# SCH_praktikum-gib-mir-mal-ne-wago_V1_0_2.net
KiCad netlist of a schematic drawn in EasyEDA
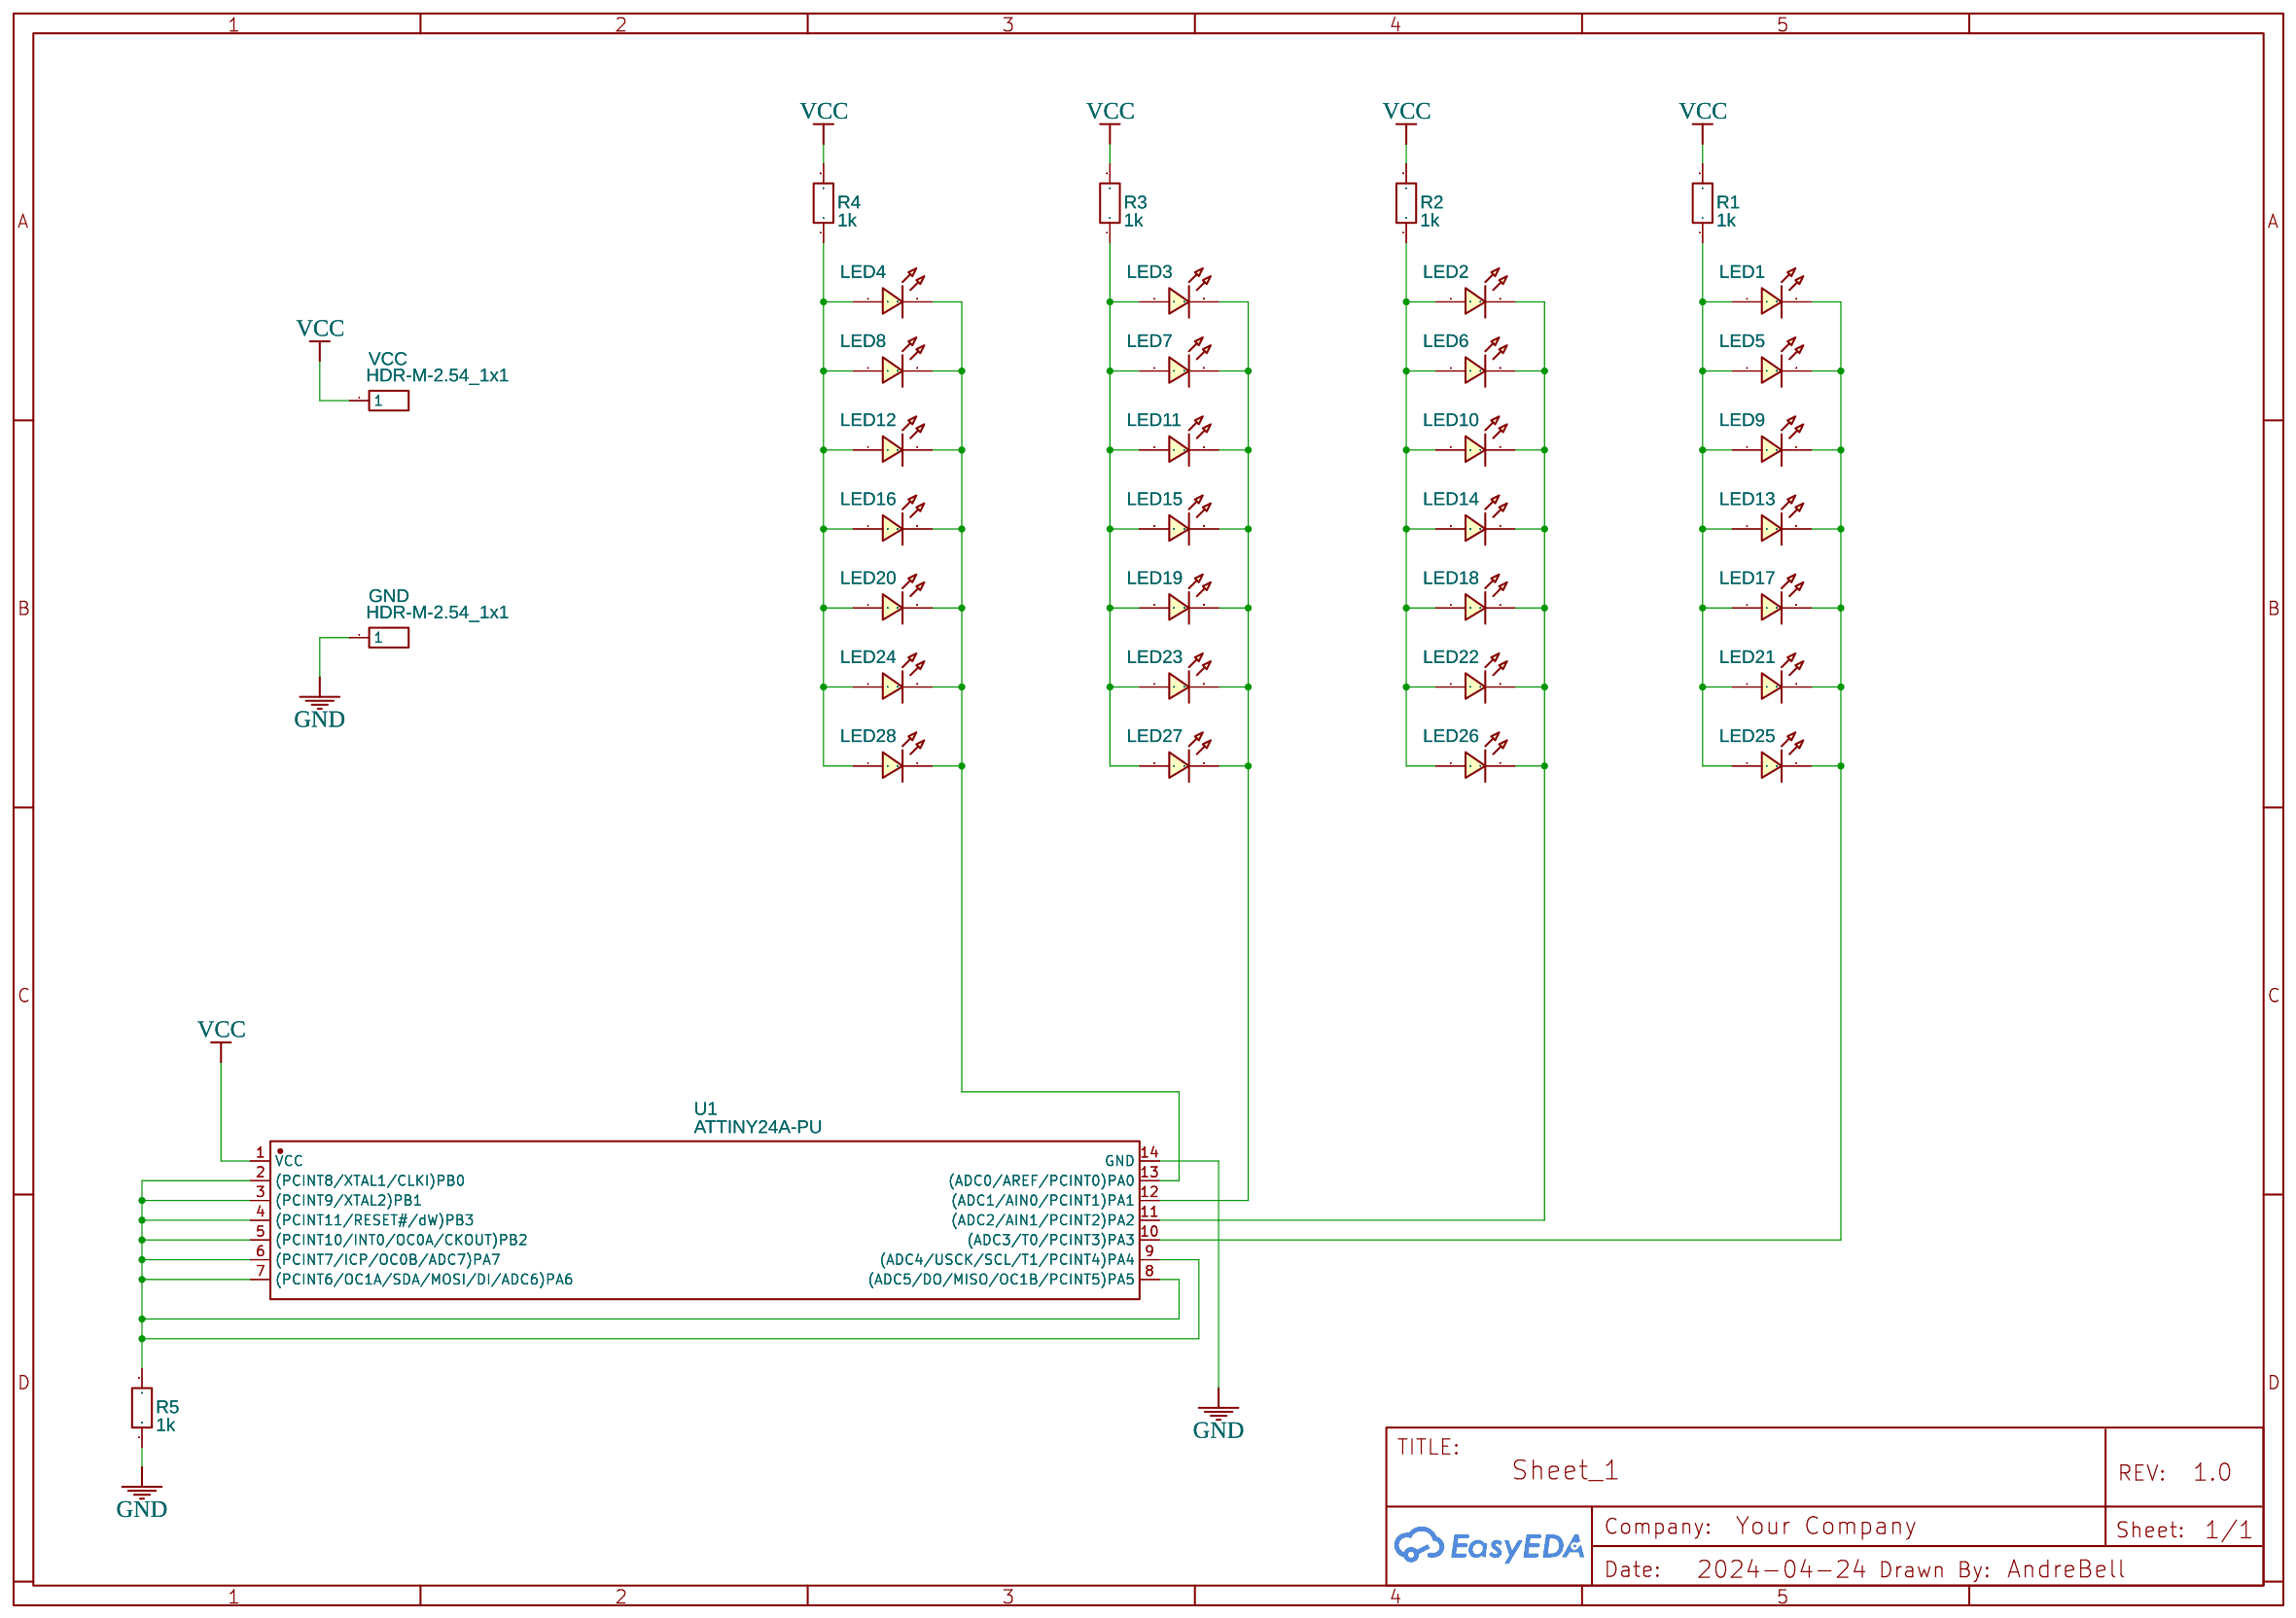
[diagram p0: schematic sheet]

(export (version "E")
  (design (tool "Eeschema 10.0.6"))
  (components
    (comp (ref "GND") (value "HDR-M-2.54_1x1") (libsource (lib "") (part "HDR-M-2.54_1x1")))
    (comp (ref "LED1")
      (value "LED-TH-3mm_G")
      (fields
        (field (name "Manufacturer Part") "204-10SYGD/S530-E3")
        (field (name "Manufacturer") "EVERLIGHT(台湾亿光)")
      )
      (libsource (lib "") (part "LED-TH-3mm_G"))
    )
    (comp (ref "LED2")
      (value "LED-TH-3mm_G")
      (fields
        (field (name "Manufacturer Part") "204-10SYGD/S530-E3")
        (field (name "Manufacturer") "EVERLIGHT(台湾亿光)")
      )
      (libsource (lib "") (part "LED-TH-3mm_G"))
    )
    (comp (ref "LED3")
      (value "LED-TH-3mm_G")
      (fields
        (field (name "Manufacturer Part") "204-10SYGD/S530-E3")
        (field (name "Manufacturer") "EVERLIGHT(台湾亿光)")
      )
      (libsource (lib "") (part "LED-TH-3mm_G"))
    )
    (comp (ref "LED4")
      (value "LED-TH-3mm_G")
      (fields
        (field (name "Manufacturer Part") "204-10SYGD/S530-E3")
        (field (name "Manufacturer") "EVERLIGHT(台湾亿光)")
      )
      (libsource (lib "") (part "LED-TH-3mm_G"))
    )
    (comp (ref "LED5")
      (value "LED-TH-3mm_G")
      (fields
        (field (name "Manufacturer Part") "204-10SYGD/S530-E3")
        (field (name "Manufacturer") "EVERLIGHT(台湾亿光)")
      )
      (libsource (lib "") (part "LED-TH-3mm_G"))
    )
    (comp (ref "LED6")
      (value "LED-TH-3mm_G")
      (fields
        (field (name "Manufacturer Part") "204-10SYGD/S530-E3")
        (field (name "Manufacturer") "EVERLIGHT(台湾亿光)")
      )
      (libsource (lib "") (part "LED-TH-3mm_G"))
    )
    (comp (ref "LED7")
      (value "LED-TH-3mm_G")
      (fields
        (field (name "Manufacturer Part") "204-10SYGD/S530-E3")
        (field (name "Manufacturer") "EVERLIGHT(台湾亿光)")
      )
      (libsource (lib "") (part "LED-TH-3mm_G"))
    )
    (comp (ref "LED8")
      (value "LED-TH-3mm_G")
      (fields
        (field (name "Manufacturer Part") "204-10SYGD/S530-E3")
        (field (name "Manufacturer") "EVERLIGHT(台湾亿光)")
      )
      (libsource (lib "") (part "LED-TH-3mm_G"))
    )
    (comp (ref "LED9")
      (value "LED-TH-3mm_G")
      (fields
        (field (name "Manufacturer Part") "204-10SYGD/S530-E3")
        (field (name "Manufacturer") "EVERLIGHT(台湾亿光)")
      )
      (libsource (lib "") (part "LED-TH-3mm_G"))
    )
    (comp (ref "LED10")
      (value "LED-TH-3mm_G")
      (fields
        (field (name "Manufacturer Part") "204-10SYGD/S530-E3")
        (field (name "Manufacturer") "EVERLIGHT(台湾亿光)")
      )
      (libsource (lib "") (part "LED-TH-3mm_G"))
    )
    (comp (ref "LED11")
      (value "LED-TH-3mm_G")
      (fields
        (field (name "Manufacturer Part") "204-10SYGD/S530-E3")
        (field (name "Manufacturer") "EVERLIGHT(台湾亿光)")
      )
      (libsource (lib "") (part "LED-TH-3mm_G"))
    )
    (comp (ref "LED12")
      (value "LED-TH-3mm_G")
      (fields
        (field (name "Manufacturer Part") "204-10SYGD/S530-E3")
        (field (name "Manufacturer") "EVERLIGHT(台湾亿光)")
      )
      (libsource (lib "") (part "LED-TH-3mm_G"))
    )
    (comp (ref "LED13")
      (value "LED-TH-3mm_G")
      (fields
        (field (name "Manufacturer Part") "204-10SYGD/S530-E3")
        (field (name "Manufacturer") "EVERLIGHT(台湾亿光)")
      )
      (libsource (lib "") (part "LED-TH-3mm_G"))
    )
    (comp (ref "LED14")
      (value "LED-TH-3mm_G")
      (fields
        (field (name "Manufacturer Part") "204-10SYGD/S530-E3")
        (field (name "Manufacturer") "EVERLIGHT(台湾亿光)")
      )
      (libsource (lib "") (part "LED-TH-3mm_G"))
    )
    (comp (ref "LED15")
      (value "LED-TH-3mm_G")
      (fields
        (field (name "Manufacturer Part") "204-10SYGD/S530-E3")
        (field (name "Manufacturer") "EVERLIGHT(台湾亿光)")
      )
      (libsource (lib "") (part "LED-TH-3mm_G"))
    )
    (comp (ref "LED16")
      (value "LED-TH-3mm_G")
      (fields
        (field (name "Manufacturer Part") "204-10SYGD/S530-E3")
        (field (name "Manufacturer") "EVERLIGHT(台湾亿光)")
      )
      (libsource (lib "") (part "LED-TH-3mm_G"))
    )
    (comp (ref "LED17")
      (value "LED-TH-3mm_G")
      (fields
        (field (name "Manufacturer Part") "204-10SYGD/S530-E3")
        (field (name "Manufacturer") "EVERLIGHT(台湾亿光)")
      )
      (libsource (lib "") (part "LED-TH-3mm_G"))
    )
    (comp (ref "LED18")
      (value "LED-TH-3mm_G")
      (fields
        (field (name "Manufacturer Part") "204-10SYGD/S530-E3")
        (field (name "Manufacturer") "EVERLIGHT(台湾亿光)")
      )
      (libsource (lib "") (part "LED-TH-3mm_G"))
    )
    (comp (ref "LED19")
      (value "LED-TH-3mm_G")
      (fields
        (field (name "Manufacturer Part") "204-10SYGD/S530-E3")
        (field (name "Manufacturer") "EVERLIGHT(台湾亿光)")
      )
      (libsource (lib "") (part "LED-TH-3mm_G"))
    )
    (comp (ref "LED20")
      (value "LED-TH-3mm_G")
      (fields
        (field (name "Manufacturer Part") "204-10SYGD/S530-E3")
        (field (name "Manufacturer") "EVERLIGHT(台湾亿光)")
      )
      (libsource (lib "") (part "LED-TH-3mm_G"))
    )
    (comp (ref "LED21")
      (value "LED-TH-3mm_G")
      (fields
        (field (name "Manufacturer Part") "204-10SYGD/S530-E3")
        (field (name "Manufacturer") "EVERLIGHT(台湾亿光)")
      )
      (libsource (lib "") (part "LED-TH-3mm_G"))
    )
    (comp (ref "LED22")
      (value "LED-TH-3mm_G")
      (fields
        (field (name "Manufacturer Part") "204-10SYGD/S530-E3")
        (field (name "Manufacturer") "EVERLIGHT(台湾亿光)")
      )
      (libsource (lib "") (part "LED-TH-3mm_G"))
    )
    (comp (ref "LED23")
      (value "LED-TH-3mm_G")
      (fields
        (field (name "Manufacturer Part") "204-10SYGD/S530-E3")
        (field (name "Manufacturer") "EVERLIGHT(台湾亿光)")
      )
      (libsource (lib "") (part "LED-TH-3mm_G"))
    )
    (comp (ref "LED24")
      (value "LED-TH-3mm_G")
      (fields
        (field (name "Manufacturer Part") "204-10SYGD/S530-E3")
        (field (name "Manufacturer") "EVERLIGHT(台湾亿光)")
      )
      (libsource (lib "") (part "LED-TH-3mm_G"))
    )
    (comp (ref "LED25")
      (value "LED-TH-3mm_G")
      (fields
        (field (name "Manufacturer Part") "204-10SYGD/S530-E3")
        (field (name "Manufacturer") "EVERLIGHT(台湾亿光)")
      )
      (libsource (lib "") (part "LED-TH-3mm_G"))
    )
    (comp (ref "LED26")
      (value "LED-TH-3mm_G")
      (fields
        (field (name "Manufacturer Part") "204-10SYGD/S530-E3")
        (field (name "Manufacturer") "EVERLIGHT(台湾亿光)")
      )
      (libsource (lib "") (part "LED-TH-3mm_G"))
    )
    (comp (ref "LED27")
      (value "LED-TH-3mm_G")
      (fields
        (field (name "Manufacturer Part") "204-10SYGD/S530-E3")
        (field (name "Manufacturer") "EVERLIGHT(台湾亿光)")
      )
      (libsource (lib "") (part "LED-TH-3mm_G"))
    )
    (comp (ref "LED28")
      (value "LED-TH-3mm_G")
      (fields
        (field (name "Manufacturer Part") "204-10SYGD/S530-E3")
        (field (name "Manufacturer") "EVERLIGHT(台湾亿光)")
      )
      (libsource (lib "") (part "LED-TH-3mm_G"))
    )
    (comp (ref "R1") (value "1k") (libsource (lib "") (part "R_AXIAL-0.3_EU")))
    (comp (ref "R2") (value "1k") (libsource (lib "") (part "R_AXIAL-0.3_EU")))
    (comp (ref "R3") (value "1k") (libsource (lib "") (part "R_AXIAL-0.3_EU")))
    (comp (ref "R4") (value "1k") (libsource (lib "") (part "R_AXIAL-0.3_EU")))
    (comp (ref "R5") (value "1k") (libsource (lib "") (part "R_AXIAL-0.3_EU")))
    (comp (ref "U1")
      (value "ATTINY24A-PU")
      (fields (field (name "Manufacturer") "MICROCHIP(美国微芯)"))
      (libsource (lib "") (part "ATTINY24A-PU"))
    )
    (comp (ref "VCC") (value "HDR-M-2.54_1x1") (libsource (lib "") (part "HDR-M-2.54_1x1_1")))
  )
  (nets
    (net (code "1") (name "GND") (class "Default")
      (node (ref "GND") (pin "1") (pinfunction "1_1") (pintype "input"))
      (node (ref "R5") (pin "1") (pinfunction "1_1") (pintype "unspecified"))
      (node (ref "U1") (pin "14") (pinfunction "GND_14") (pintype "unspecified"))
    )
    (net (code "2") (name "Net-(LED1-Pad1)") (class "Default")
      (node (ref "LED1") (pin "1") (pinfunction "1_1") (pintype "unspecified"))
      (node (ref "LED13") (pin "1") (pinfunction "1_1") (pintype "unspecified"))
      (node (ref "LED17") (pin "1") (pinfunction "1_1") (pintype "unspecified"))
      (node (ref "LED21") (pin "1") (pinfunction "1_1") (pintype "unspecified"))
      (node (ref "LED25") (pin "1") (pinfunction "1_1") (pintype "unspecified"))
      (node (ref "LED5") (pin "1") (pinfunction "1_1") (pintype "unspecified"))
      (node (ref "LED9") (pin "1") (pinfunction "1_1") (pintype "unspecified"))
      (node (ref "R1") (pin "1") (pinfunction "1_1") (pintype "unspecified"))
    )
    (net (code "3") (name "Net-(LED10-Pad1)") (class "Default")
      (node (ref "LED10") (pin "1") (pinfunction "1_1") (pintype "unspecified"))
      (node (ref "LED14") (pin "1") (pinfunction "1_1") (pintype "unspecified"))
      (node (ref "LED18") (pin "1") (pinfunction "1_1") (pintype "unspecified"))
      (node (ref "LED2") (pin "1") (pinfunction "1_1") (pintype "unspecified"))
      (node (ref "LED22") (pin "1") (pinfunction "1_1") (pintype "unspecified"))
      (node (ref "LED26") (pin "1") (pinfunction "1_1") (pintype "unspecified"))
      (node (ref "LED6") (pin "1") (pinfunction "1_1") (pintype "unspecified"))
      (node (ref "R2") (pin "1") (pinfunction "1_1") (pintype "unspecified"))
    )
    (net (code "4") (name "Net-(LED11-Pad1)") (class "Default")
      (node (ref "LED11") (pin "1") (pinfunction "1_1") (pintype "unspecified"))
      (node (ref "LED15") (pin "1") (pinfunction "1_1") (pintype "unspecified"))
      (node (ref "LED19") (pin "1") (pinfunction "1_1") (pintype "unspecified"))
      (node (ref "LED23") (pin "1") (pinfunction "1_1") (pintype "unspecified"))
      (node (ref "LED27") (pin "1") (pinfunction "1_1") (pintype "unspecified"))
      (node (ref "LED3") (pin "1") (pinfunction "1_1") (pintype "unspecified"))
      (node (ref "LED7") (pin "1") (pinfunction "1_1") (pintype "unspecified"))
      (node (ref "R3") (pin "1") (pinfunction "1_1") (pintype "unspecified"))
    )
    (net (code "5") (name "Net-(LED12-Pad1)") (class "Default")
      (node (ref "LED12") (pin "1") (pinfunction "1_1") (pintype "unspecified"))
      (node (ref "LED16") (pin "1") (pinfunction "1_1") (pintype "unspecified"))
      (node (ref "LED20") (pin "1") (pinfunction "1_1") (pintype "unspecified"))
      (node (ref "LED24") (pin "1") (pinfunction "1_1") (pintype "unspecified"))
      (node (ref "LED28") (pin "1") (pinfunction "1_1") (pintype "unspecified"))
      (node (ref "LED4") (pin "1") (pinfunction "1_1") (pintype "unspecified"))
      (node (ref "LED8") (pin "1") (pinfunction "1_1") (pintype "unspecified"))
      (node (ref "R4") (pin "1") (pinfunction "1_1") (pintype "unspecified"))
    )
    (net (code "6") (name "Net-(U1-(ADC0{slash}AREF{slash}PCINT0)PA0)") (class "Default")
      (node (ref "LED12") (pin "2") (pinfunction "2_2") (pintype "unspecified"))
      (node (ref "LED16") (pin "2") (pinfunction "2_2") (pintype "unspecified"))
      (node (ref "LED20") (pin "2") (pinfunction "2_2") (pintype "unspecified"))
      (node (ref "LED24") (pin "2") (pinfunction "2_2") (pintype "unspecified"))
      (node (ref "LED28") (pin "2") (pinfunction "2_2") (pintype "unspecified"))
      (node (ref "LED4") (pin "2") (pinfunction "2_2") (pintype "unspecified"))
      (node (ref "LED8") (pin "2") (pinfunction "2_2") (pintype "unspecified"))
      (node (ref "U1") (pin "13") (pinfunction "(ADC0/AREF/PCINT0)PA0_13") (pintype "unspecified"))
    )
    (net (code "7") (name "Net-(U1-(ADC1{slash}AIN0{slash}PCINT1)PA1)") (class "Default")
      (node (ref "LED11") (pin "2") (pinfunction "2_2") (pintype "unspecified"))
      (node (ref "LED15") (pin "2") (pinfunction "2_2") (pintype "unspecified"))
      (node (ref "LED19") (pin "2") (pinfunction "2_2") (pintype "unspecified"))
      (node (ref "LED23") (pin "2") (pinfunction "2_2") (pintype "unspecified"))
      (node (ref "LED27") (pin "2") (pinfunction "2_2") (pintype "unspecified"))
      (node (ref "LED3") (pin "2") (pinfunction "2_2") (pintype "unspecified"))
      (node (ref "LED7") (pin "2") (pinfunction "2_2") (pintype "unspecified"))
      (node (ref "U1") (pin "12") (pinfunction "(ADC1/AIN0/PCINT1)PA1_12") (pintype "unspecified"))
    )
    (net (code "8") (name "Net-(U1-(ADC2{slash}AIN1{slash}PCINT2)PA2)") (class "Default")
      (node (ref "LED10") (pin "2") (pinfunction "2_2") (pintype "unspecified"))
      (node (ref "LED14") (pin "2") (pinfunction "2_2") (pintype "unspecified"))
      (node (ref "LED18") (pin "2") (pinfunction "2_2") (pintype "unspecified"))
      (node (ref "LED2") (pin "2") (pinfunction "2_2") (pintype "unspecified"))
      (node (ref "LED22") (pin "2") (pinfunction "2_2") (pintype "unspecified"))
      (node (ref "LED26") (pin "2") (pinfunction "2_2") (pintype "unspecified"))
      (node (ref "LED6") (pin "2") (pinfunction "2_2") (pintype "unspecified"))
      (node (ref "U1") (pin "11") (pinfunction "(ADC2/AIN1/PCINT2)PA2_11") (pintype "unspecified"))
    )
    (net (code "9") (name "Net-(U1-(ADC3{slash}T0{slash}PCINT3)PA3)") (class "Default")
      (node (ref "LED1") (pin "2") (pinfunction "2_2") (pintype "unspecified"))
      (node (ref "LED13") (pin "2") (pinfunction "2_2") (pintype "unspecified"))
      (node (ref "LED17") (pin "2") (pinfunction "2_2") (pintype "unspecified"))
      (node (ref "LED21") (pin "2") (pinfunction "2_2") (pintype "unspecified"))
      (node (ref "LED25") (pin "2") (pinfunction "2_2") (pintype "unspecified"))
      (node (ref "LED5") (pin "2") (pinfunction "2_2") (pintype "unspecified"))
      (node (ref "LED9") (pin "2") (pinfunction "2_2") (pintype "unspecified"))
      (node (ref "U1") (pin "10") (pinfunction "(ADC3/T0/PCINT3)PA3_10") (pintype "unspecified"))
    )
    (net (code "10") (name "Net-(U1-(ADC4{slash}USCK{slash}SCL{slash}T1{slash}PCINT4)PA4)") (class "Default")
      (node (ref "R5") (pin "2") (pinfunction "2_2") (pintype "unspecified"))
      (node (ref "U1") (pin "2") (pinfunction "(PCINT8/XTAL1/CLKI)PB0_2") (pintype "unspecified"))
      (node (ref "U1") (pin "3") (pinfunction "(PCINT9/XTAL2)PB1_3") (pintype "unspecified"))
      (node (ref "U1") (pin "4") (pinfunction "(PCINT11/RESET#/dW)PB3_4") (pintype "unspecified"))
      (node (ref "U1") (pin "5") (pinfunction "(PCINT10/INT0/OC0A/CKOUT)PB2_5") (pintype "unspecified"))
      (node (ref "U1") (pin "6") (pinfunction "(PCINT7/ICP/OC0B/ADC7)PA7_6") (pintype "unspecified"))
      (node (ref "U1") (pin "7") (pinfunction "(PCINT6/OC1A/SDA/MOSI/DI/ADC6)PA6_7") (pintype "unspecified"))
      (node (ref "U1") (pin "8") (pinfunction "(ADC5/DO/MISO/OC1B/PCINT5)PA5_8") (pintype "unspecified"))
      (node (ref "U1") (pin "9") (pinfunction "(ADC4/USCK/SCL/T1/PCINT4)PA4_9") (pintype "unspecified"))
    )
    (net (code "11") (name "VCC") (class "Default")
      (node (ref "R1") (pin "2") (pinfunction "2_2") (pintype "unspecified"))
      (node (ref "R2") (pin "2") (pinfunction "2_2") (pintype "unspecified"))
      (node (ref "R3") (pin "2") (pinfunction "2_2") (pintype "unspecified"))
      (node (ref "R4") (pin "2") (pinfunction "2_2") (pintype "unspecified"))
      (node (ref "U1") (pin "1") (pinfunction "VCC_1") (pintype "unspecified"))
      (node (ref "VCC") (pin "1") (pinfunction "1_1") (pintype "input"))
    )
  )
)
